# 4_3_MCU_RGB.net
KiCad netlist of a schematic drawn in Altium Designer
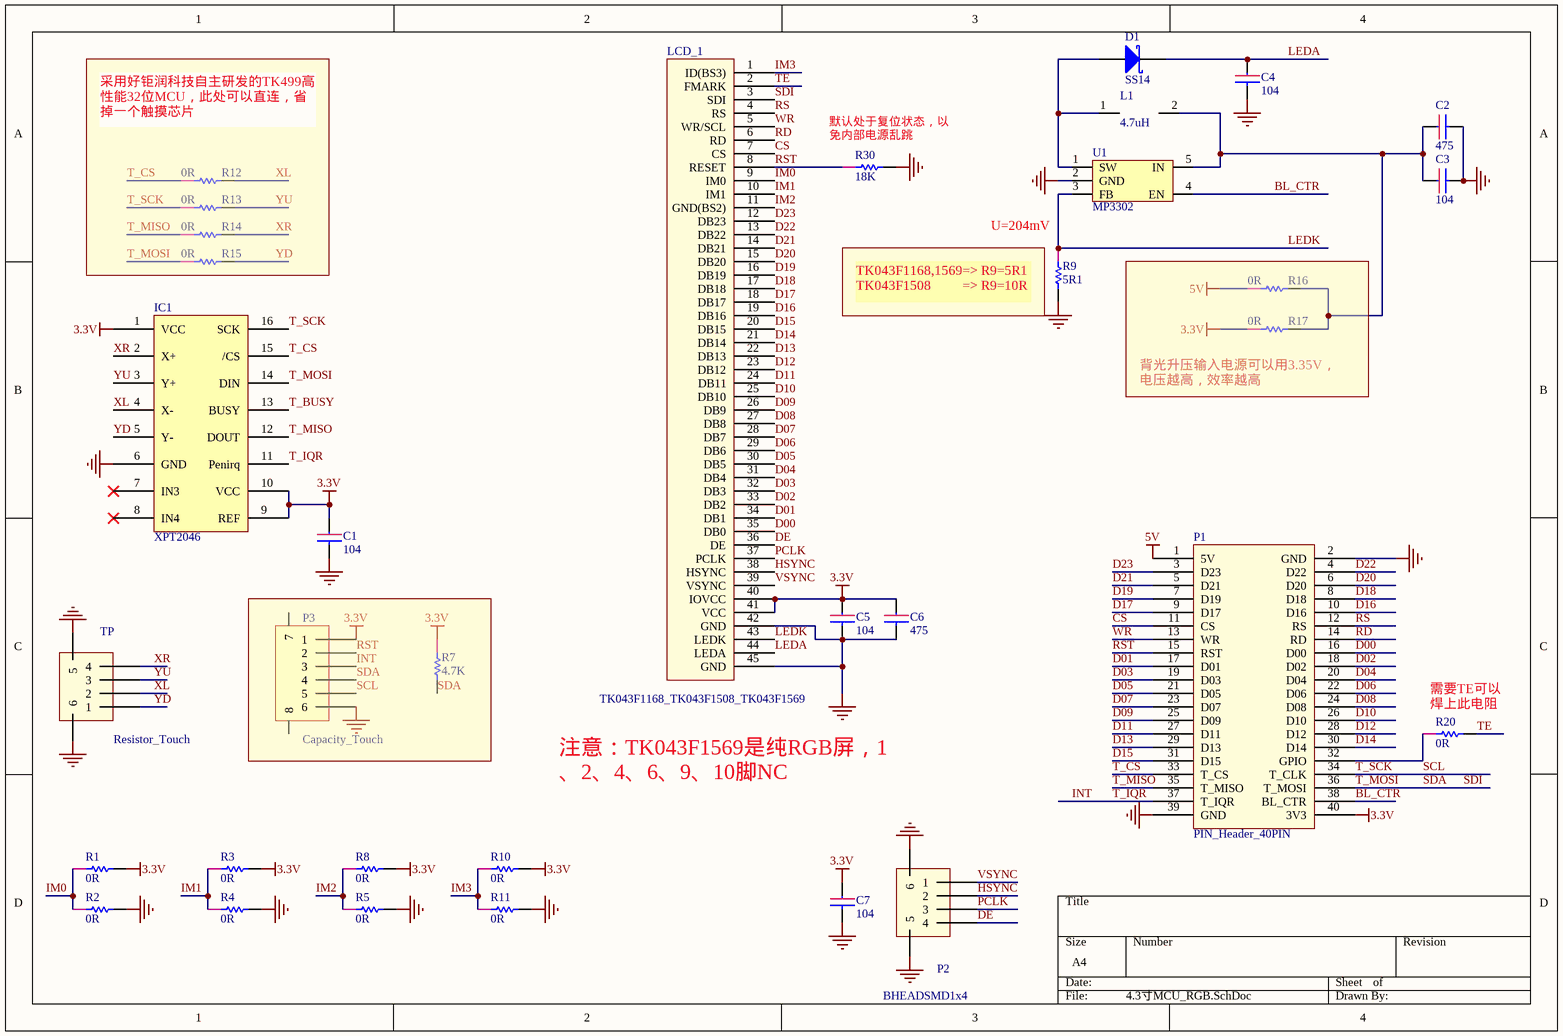
[diagram p0: 4.3寸MCU_RGB.SchDoc]

(export (version "E")
  (design (tool "Eeschema 10.0.6"))
  (components
    (comp (ref "C1") (value "104") (footprint "C0603-1") (libsource (lib "Tiky") (part "cap")))
    (comp (ref "C2") (value "475") (footprint "C0603-2") (libsource (lib "Tiky") (part "cap")))
    (comp (ref "C3") (value "104") (footprint "C0603-1") (libsource (lib "Tiky") (part "cap")))
    (comp (ref "C4") (value "104") (footprint "C0603-2") (libsource (lib "Tiky") (part "cap")))
    (comp (ref "C5") (value "104") (footprint "C0603-1") (libsource (lib "Tiky") (part "cap")))
    (comp (ref "C6") (value "475") (footprint "C0603-2") (libsource (lib "Tiky") (part "cap")))
    (comp (ref "C7") (value "104") (footprint "C0603-1") (libsource (lib "Tiky") (part "cap")))
    (comp (ref "D1")
      (value "SS14")
      (footprint "SOD123")
      (description "Schottky Diode")
      (fields (field (name "PUBLISHER") "Altium Limited"))
      (libsource (lib "Miscellaneous Devices") (part "D Schottky"))
    )
    (comp (ref "IC1") (value "XPT2046") (footprint "SOT403-1") (libsource (lib "Tiky") (part "ADS7843")))
    (comp (ref "L1") (value "4.7uH") (footprint "L1206") (libsource (lib "Tiky") (part "Inductor")))
    (comp (ref "LCD_1")
      (value "TK043F1168_TK043F1508_TK043F1569")
      (footprint "TFT_KGM1066A0")
      (libsource (lib "Tiky") (part "TK043F1168"))
    )
    (comp (ref "P1")
      (value "PIN_Header_40PIN")
      (footprint "P_Head_2x20")
      (libsource (lib "Tiky") (part "PIN_Header_40PIN"))
    )
    (comp (ref "P2")
      (value "BHEADSMD1x4")
      (footprint "BHEADSMD1x4")
      (libsource (lib "") (part "BHEADSMD1x4_1"))
    )
    (comp (ref "P3")
      (value "Capacity_Touch")
      (footprint "TP_Cap_4.3inch")
      (libsource (lib "Tiky") (part "BHEADSMD1x6"))
    )
    (comp (ref "R1") (value "0R") (footprint "R0603") (libsource (lib "Tiky") (part "Resistor")))
    (comp (ref "R2") (value "0R") (footprint "R0603") (libsource (lib "Tiky") (part "Resistor")))
    (comp (ref "R3") (value "0R") (footprint "R0603") (libsource (lib "Tiky") (part "Resistor")))
    (comp (ref "R4") (value "0R") (footprint "R0603") (libsource (lib "Tiky") (part "Resistor")))
    (comp (ref "R5") (value "0R") (footprint "R0603") (libsource (lib "Tiky") (part "Resistor")))
    (comp (ref "R7") (value "4.7K") (footprint "R0603") (libsource (lib "Tiky") (part "Resistor")))
    (comp (ref "R8") (value "0R") (footprint "R0603") (libsource (lib "Tiky") (part "Resistor")))
    (comp (ref "R9") (value "5R1") (footprint "R0603") (libsource (lib "Tiky") (part "Resistor")))
    (comp (ref "R10") (value "0R") (footprint "R0603") (libsource (lib "Tiky") (part "Resistor")))
    (comp (ref "R11") (value "0R") (footprint "R0603") (libsource (lib "Tiky") (part "Resistor")))
    (comp (ref "R12") (value "0R") (footprint "R0402") (libsource (lib "Tiky") (part "Resistor")))
    (comp (ref "R13") (value "0R") (footprint "R0402") (libsource (lib "Tiky") (part "Resistor")))
    (comp (ref "R14") (value "0R") (footprint "R0402") (libsource (lib "Tiky") (part "Resistor")))
    (comp (ref "R15") (value "0R") (footprint "R0402") (libsource (lib "Tiky") (part "Resistor")))
    (comp (ref "R16") (value "0R") (footprint "R0603") (libsource (lib "Tiky") (part "Resistor")))
    (comp (ref "R17") (value "0R") (footprint "R0603") (libsource (lib "Tiky") (part "Resistor")))
    (comp (ref "R20") (value "0R") (footprint "R0603") (libsource (lib "Tiky") (part "Resistor")))
    (comp (ref "R30") (value "18K") (footprint "R0603") (libsource (lib "Tiky") (part "Resistor")))
    (comp (ref "TP")
      (value "Resistor_Touch")
      (footprint "TP_5.0inch")
      (libsource (lib "Tiky") (part "BHEADSMD1x4"))
    )
    (comp (ref "U1") (value "MP3302") (footprint "SOT23-5") (libsource (lib "Tiky") (part "MP3302")))
  )
  (nets
    (net (code "1") (name "/BL_CTR") (class "Default")
      (node (ref "P1") (pin "38") (pinfunction "BL_CTR_38") (pintype "passive"))
      (node (ref "U1") (pin "4") (pinfunction "EN_4") (pintype "passive"))
    )
    (net (code "2") (name "/CS") (class "Default")
      (node (ref "LCD_1") (pin "7") (pinfunction "CS_7") (pintype "passive"))
      (node (ref "P1") (pin "11") (pinfunction "CS_11") (pintype "passive"))
    )
    (net (code "3") (name "/D00") (class "Default")
      (node (ref "LCD_1") (pin "35") (pinfunction "DB0_35") (pintype "passive"))
      (node (ref "P1") (pin "16") (pinfunction "D00_16") (pintype "passive"))
    )
    (net (code "4") (name "/D01") (class "Default")
      (node (ref "LCD_1") (pin "34") (pinfunction "DB1_34") (pintype "passive"))
      (node (ref "P1") (pin "17") (pinfunction "D01_17") (pintype "passive"))
    )
    (net (code "5") (name "/D02") (class "Default")
      (node (ref "LCD_1") (pin "33") (pinfunction "DB2_33") (pintype "passive"))
      (node (ref "P1") (pin "18") (pinfunction "D02_18") (pintype "passive"))
    )
    (net (code "6") (name "/D03") (class "Default")
      (node (ref "LCD_1") (pin "32") (pinfunction "DB3_32") (pintype "passive"))
      (node (ref "P1") (pin "19") (pinfunction "D03_19") (pintype "passive"))
    )
    (net (code "7") (name "/D04") (class "Default")
      (node (ref "LCD_1") (pin "31") (pinfunction "DB4_31") (pintype "passive"))
      (node (ref "P1") (pin "20") (pinfunction "D04_20") (pintype "passive"))
    )
    (net (code "8") (name "/D05") (class "Default")
      (node (ref "LCD_1") (pin "30") (pinfunction "DB5_30") (pintype "passive"))
      (node (ref "P1") (pin "21") (pinfunction "D05_21") (pintype "passive"))
    )
    (net (code "9") (name "/D06") (class "Default")
      (node (ref "LCD_1") (pin "29") (pinfunction "DB6_29") (pintype "passive"))
      (node (ref "P1") (pin "22") (pinfunction "D06_22") (pintype "passive"))
    )
    (net (code "10") (name "/D07") (class "Default")
      (node (ref "LCD_1") (pin "28") (pinfunction "DB7_28") (pintype "passive"))
      (node (ref "P1") (pin "23") (pinfunction "D07_23") (pintype "passive"))
    )
    (net (code "11") (name "/D08") (class "Default")
      (node (ref "LCD_1") (pin "27") (pinfunction "DB8_27") (pintype "passive"))
      (node (ref "P1") (pin "24") (pinfunction "D08_24") (pintype "passive"))
    )
    (net (code "12") (name "/D09") (class "Default")
      (node (ref "LCD_1") (pin "26") (pinfunction "DB9_26") (pintype "passive"))
      (node (ref "P1") (pin "25") (pinfunction "D09_25") (pintype "passive"))
    )
    (net (code "13") (name "/D10") (class "Default")
      (node (ref "LCD_1") (pin "25") (pinfunction "DB10_25") (pintype "passive"))
      (node (ref "P1") (pin "26") (pinfunction "D10_26") (pintype "passive"))
    )
    (net (code "14") (name "/D11") (class "Default")
      (node (ref "LCD_1") (pin "24") (pinfunction "DB11_24") (pintype "passive"))
      (node (ref "P1") (pin "27") (pinfunction "D11_27") (pintype "passive"))
    )
    (net (code "15") (name "/D12") (class "Default")
      (node (ref "LCD_1") (pin "23") (pinfunction "DB12_23") (pintype "passive"))
      (node (ref "P1") (pin "28") (pinfunction "D12_28") (pintype "passive"))
    )
    (net (code "16") (name "/D13") (class "Default")
      (node (ref "LCD_1") (pin "22") (pinfunction "DB13_22") (pintype "passive"))
      (node (ref "P1") (pin "29") (pinfunction "D13_29") (pintype "passive"))
    )
    (net (code "17") (name "/D14") (class "Default")
      (node (ref "LCD_1") (pin "21") (pinfunction "DB14_21") (pintype "passive"))
      (node (ref "P1") (pin "30") (pinfunction "D14_30") (pintype "passive"))
    )
    (net (code "18") (name "/D15") (class "Default")
      (node (ref "LCD_1") (pin "20") (pinfunction "DB15_20") (pintype "passive"))
      (node (ref "P1") (pin "31") (pinfunction "D15_31") (pintype "passive"))
    )
    (net (code "19") (name "/D16") (class "Default")
      (node (ref "LCD_1") (pin "19") (pinfunction "DB16_19") (pintype "passive"))
      (node (ref "P1") (pin "10") (pinfunction "D16_10") (pintype "passive"))
    )
    (net (code "20") (name "/D17") (class "Default")
      (node (ref "LCD_1") (pin "18") (pinfunction "DB17_18") (pintype "passive"))
      (node (ref "P1") (pin "9") (pinfunction "D17_9") (pintype "passive"))
    )
    (net (code "21") (name "/D18") (class "Default")
      (node (ref "LCD_1") (pin "17") (pinfunction "DB18_17") (pintype "passive"))
      (node (ref "P1") (pin "8") (pinfunction "D18_8") (pintype "passive"))
    )
    (net (code "22") (name "/D19") (class "Default")
      (node (ref "LCD_1") (pin "16") (pinfunction "DB19_16") (pintype "passive"))
      (node (ref "P1") (pin "7") (pinfunction "D19_7") (pintype "passive"))
    )
    (net (code "23") (name "/D20") (class "Default")
      (node (ref "LCD_1") (pin "15") (pinfunction "DB20_15") (pintype "passive"))
      (node (ref "P1") (pin "6") (pinfunction "D20_6") (pintype "passive"))
    )
    (net (code "24") (name "/D21") (class "Default")
      (node (ref "LCD_1") (pin "14") (pinfunction "DB21_14") (pintype "passive"))
      (node (ref "P1") (pin "5") (pinfunction "D21_5") (pintype "passive"))
    )
    (net (code "25") (name "/D22") (class "Default")
      (node (ref "LCD_1") (pin "13") (pinfunction "DB22_13") (pintype "passive"))
      (node (ref "P1") (pin "4") (pinfunction "D22_4") (pintype "passive"))
    )
    (net (code "26") (name "/D23") (class "Default")
      (node (ref "LCD_1") (pin "12") (pinfunction "DB23_12") (pintype "passive"))
      (node (ref "P1") (pin "3") (pinfunction "D23_3") (pintype "passive"))
    )
    (net (code "27") (name "/DE") (class "Default")
      (node (ref "LCD_1") (pin "36") (pinfunction "DE_36") (pintype "passive"))
      (node (ref "P2") (pin "4") (pinfunction "4_4") (pintype "passive"))
    )
    (net (code "28") (name "/HSYNC") (class "Default")
      (node (ref "LCD_1") (pin "38") (pinfunction "HSYNC_38") (pintype "passive"))
      (node (ref "P2") (pin "2") (pinfunction "2_2") (pintype "passive"))
    )
    (net (code "29") (name "/IM0") (class "Default")
      (node (ref "LCD_1") (pin "9") (pinfunction "IM0_9") (pintype "passive"))
      (node (ref "R1") (pin "1") (pinfunction "1_1") (pintype "passive"))
      (node (ref "R2") (pin "1") (pinfunction "1_1") (pintype "passive"))
    )
    (net (code "30") (name "/IM1") (class "Default")
      (node (ref "LCD_1") (pin "10") (pinfunction "IM1_10") (pintype "passive"))
      (node (ref "R3") (pin "1") (pinfunction "1_1") (pintype "passive"))
      (node (ref "R4") (pin "1") (pinfunction "1_1") (pintype "passive"))
    )
    (net (code "31") (name "/IM2") (class "Default")
      (node (ref "LCD_1") (pin "11") (pinfunction "GND(BS2)_11") (pintype "passive"))
      (node (ref "R5") (pin "1") (pinfunction "1_1") (pintype "passive"))
      (node (ref "R8") (pin "1") (pinfunction "1_1") (pintype "passive"))
    )
    (net (code "32") (name "/IM3") (class "Default")
      (node (ref "LCD_1") (pin "1") (pinfunction "ID(BS3)_1") (pintype "passive"))
      (node (ref "R10") (pin "1") (pinfunction "1_1") (pintype "passive"))
      (node (ref "R11") (pin "1") (pinfunction "1_1") (pintype "passive"))
    )
    (net (code "33") (name "/INT") (class "Default")
      (node (ref "IC1") (pin "11") (pinfunction "Penirq_11") (pintype "passive"))
      (node (ref "P1") (pin "37") (pinfunction "T_IQR_37") (pintype "passive"))
      (node (ref "P3") (pin "3") (pinfunction "3_3") (pintype "passive"))
    )
    (net (code "34") (name "/LEDA") (class "Default")
      (node (ref "C4") (pin "1") (pinfunction "1_1") (pintype "passive"))
      (node (ref "D1") (pin "2") (pinfunction "K_2") (pintype "passive"))
      (node (ref "LCD_1") (pin "44") (pinfunction "LEDA_44") (pintype "passive"))
    )
    (net (code "35") (name "/LEDK") (class "Default")
      (node (ref "LCD_1") (pin "43") (pinfunction "LEDK_43") (pintype "passive"))
      (node (ref "R9") (pin "1") (pinfunction "1_1") (pintype "passive"))
      (node (ref "U1") (pin "3") (pinfunction "FB_3") (pintype "passive"))
    )
    (net (code "36") (name "/PCLK") (class "Default")
      (node (ref "LCD_1") (pin "37") (pinfunction "PCLK_37") (pintype "passive"))
      (node (ref "P2") (pin "3") (pinfunction "3_3") (pintype "passive"))
    )
    (net (code "37") (name "/RD") (class "Default")
      (node (ref "LCD_1") (pin "6") (pinfunction "RD_6") (pintype "passive"))
      (node (ref "P1") (pin "14") (pinfunction "RD_14") (pintype "passive"))
    )
    (net (code "38") (name "/RS") (class "Default")
      (node (ref "LCD_1") (pin "4") (pinfunction "RS_4") (pintype "passive"))
      (node (ref "P1") (pin "12") (pinfunction "RS_12") (pintype "passive"))
    )
    (net (code "39") (name "/RST") (class "Default")
      (node (ref "LCD_1") (pin "8") (pinfunction "RESET_8") (pintype "passive"))
      (node (ref "P1") (pin "15") (pinfunction "RST_15") (pintype "passive"))
      (node (ref "P3") (pin "2") (pinfunction "2_2") (pintype "passive"))
      (node (ref "R30") (pin "1") (pinfunction "1_1") (pintype "passive"))
    )
    (net (code "40") (name "/SCL") (class "Default")
      (node (ref "IC1") (pin "16") (pinfunction "SCK_16") (pintype "passive"))
      (node (ref "P1") (pin "34") (pinfunction "T_CLK_34") (pintype "passive"))
      (node (ref "P3") (pin "5") (pinfunction "5_5") (pintype "passive"))
      (node (ref "R13") (pin "1") (pinfunction "1_1") (pintype "passive"))
    )
    (net (code "41") (name "/SDA") (class "Default")
      (node (ref "IC1") (pin "14") (pinfunction "DIN_14") (pintype "passive"))
      (node (ref "LCD_1") (pin "3") (pinfunction "SDI_3") (pintype "passive"))
      (node (ref "P1") (pin "36") (pinfunction "T_MOSI_36") (pintype "passive"))
      (node (ref "P3") (pin "4") (pinfunction "4_4") (pintype "passive"))
      (node (ref "R15") (pin "1") (pinfunction "1_1") (pintype "passive"))
      (node (ref "R7") (pin "2") (pinfunction "2_2") (pintype "passive"))
    )
    (net (code "42") (name "/TE") (class "Default")
      (node (ref "LCD_1") (pin "2") (pinfunction "FMARK_2") (pintype "passive"))
      (node (ref "R20") (pin "2") (pinfunction "2_2") (pintype "passive"))
    )
    (net (code "43") (name "/T_BUSY") (class "Default")
      (node (ref "IC1") (pin "13") (pinfunction "BUSY_13") (pintype "passive"))
    )
    (net (code "44") (name "/T_CS") (class "Default")
      (node (ref "IC1") (pin "15") (pinfunction "/CS_15") (pintype "passive"))
      (node (ref "P1") (pin "33") (pinfunction "T_CS_33") (pintype "passive"))
      (node (ref "R12") (pin "1") (pinfunction "1_1") (pintype "passive"))
    )
    (net (code "45") (name "/T_MISO") (class "Default")
      (node (ref "IC1") (pin "12") (pinfunction "DOUT_12") (pintype "passive"))
      (node (ref "P1") (pin "35") (pinfunction "T_MISO_35") (pintype "passive"))
      (node (ref "R14") (pin "1") (pinfunction "1_1") (pintype "passive"))
    )
    (net (code "46") (name "/VSYNC") (class "Default")
      (node (ref "LCD_1") (pin "39") (pinfunction "VSYNC_39") (pintype "passive"))
      (node (ref "P2") (pin "1") (pinfunction "1_1") (pintype "passive"))
    )
    (net (code "47") (name "/WR") (class "Default")
      (node (ref "LCD_1") (pin "5") (pinfunction "WR/SCL_5") (pintype "passive"))
      (node (ref "P1") (pin "13") (pinfunction "WR_13") (pintype "passive"))
    )
    (net (code "48") (name "/XL") (class "Default")
      (node (ref "IC1") (pin "4") (pinfunction "X-_4") (pintype "passive"))
      (node (ref "R12") (pin "2") (pinfunction "2_2") (pintype "passive"))
      (node (ref "TP") (pin "2") (pinfunction "2_2") (pintype "passive"))
    )
    (net (code "49") (name "/XR") (class "Default")
      (node (ref "IC1") (pin "2") (pinfunction "X+_2") (pintype "passive"))
      (node (ref "R14") (pin "2") (pinfunction "2_2") (pintype "passive"))
      (node (ref "TP") (pin "4") (pinfunction "4_4") (pintype "passive"))
    )
    (net (code "50") (name "/YD") (class "Default")
      (node (ref "IC1") (pin "5") (pinfunction "Y-_5") (pintype "passive"))
      (node (ref "R15") (pin "2") (pinfunction "2_2") (pintype "passive"))
      (node (ref "TP") (pin "1") (pinfunction "1_1") (pintype "passive"))
    )
    (net (code "51") (name "/YU") (class "Default")
      (node (ref "IC1") (pin "3") (pinfunction "Y+_3") (pintype "passive"))
      (node (ref "R13") (pin "2") (pinfunction "2_2") (pintype "passive"))
      (node (ref "TP") (pin "3") (pinfunction "3_3") (pintype "passive"))
    )
    (net (code "52") (name "3.3V") (class "Default")
      (node (ref "C1") (pin "1") (pinfunction "1_1") (pintype "passive"))
      (node (ref "C5") (pin "1") (pinfunction "1_1") (pintype "passive"))
      (node (ref "C6") (pin "1") (pinfunction "1_1") (pintype "passive"))
      (node (ref "C7") (pin "1") (pinfunction "1_1") (pintype "passive"))
      (node (ref "IC1") (pin "1") (pinfunction "VCC_1") (pintype "passive"))
      (node (ref "IC1") (pin "10") (pinfunction "VCC_10") (pintype "passive"))
      (node (ref "IC1") (pin "9") (pinfunction "REF_9") (pintype "passive"))
      (node (ref "LCD_1") (pin "40") (pinfunction "IOVCC_40") (pintype "passive"))
      (node (ref "LCD_1") (pin "41") (pinfunction "VCC_41") (pintype "passive"))
      (node (ref "P1") (pin "40") (pinfunction "3V3_40") (pintype "passive"))
      (node (ref "P3") (pin "1") (pinfunction "1_1") (pintype "passive"))
      (node (ref "R1") (pin "2") (pinfunction "2_2") (pintype "passive"))
      (node (ref "R10") (pin "2") (pinfunction "2_2") (pintype "passive"))
      (node (ref "R17") (pin "1") (pinfunction "1_1") (pintype "passive"))
      (node (ref "R3") (pin "2") (pinfunction "2_2") (pintype "passive"))
      (node (ref "R7") (pin "1") (pinfunction "1_1") (pintype "passive"))
      (node (ref "R8") (pin "2") (pinfunction "2_2") (pintype "passive"))
    )
    (net (code "53") (name "5V") (class "Default")
      (node (ref "P1") (pin "1") (pinfunction "5V_1") (pintype "passive"))
      (node (ref "R16") (pin "1") (pinfunction "1_1") (pintype "passive"))
    )
    (net (code "54") (name "GND") (class "Default")
      (node (ref "C1") (pin "2") (pinfunction "2_2") (pintype "passive"))
      (node (ref "C2") (pin "2") (pinfunction "2_2") (pintype "passive"))
      (node (ref "C3") (pin "2") (pinfunction "2_2") (pintype "passive"))
      (node (ref "C4") (pin "2") (pinfunction "2_2") (pintype "passive"))
      (node (ref "C5") (pin "2") (pinfunction "2_2") (pintype "passive"))
      (node (ref "C6") (pin "2") (pinfunction "2_2") (pintype "passive"))
      (node (ref "C7") (pin "2") (pinfunction "2_2") (pintype "passive"))
      (node (ref "IC1") (pin "6") (pinfunction "GND_6") (pintype "passive"))
      (node (ref "LCD_1") (pin "42") (pinfunction "GND_42") (pintype "passive"))
      (node (ref "LCD_1") (pin "45") (pinfunction "GND_45") (pintype "passive"))
      (node (ref "P1") (pin "2") (pinfunction "GND_2") (pintype "passive"))
      (node (ref "P1") (pin "39") (pinfunction "GND_39") (pintype "passive"))
      (node (ref "P2") (pin "5") (pinfunction "5_5") (pintype "passive"))
      (node (ref "P2") (pin "6") (pinfunction "6_6") (pintype "passive"))
      (node (ref "P3") (pin "6") (pinfunction "6_6") (pintype "passive"))
      (node (ref "R11") (pin "2") (pinfunction "2_2") (pintype "passive"))
      (node (ref "R2") (pin "2") (pinfunction "2_2") (pintype "passive"))
      (node (ref "R30") (pin "2") (pinfunction "2_2") (pintype "passive"))
      (node (ref "R4") (pin "2") (pinfunction "2_2") (pintype "passive"))
      (node (ref "R5") (pin "2") (pinfunction "2_2") (pintype "passive"))
      (node (ref "R9") (pin "2") (pinfunction "2_2") (pintype "passive"))
      (node (ref "TP") (pin "5") (pinfunction "5_5") (pintype "passive"))
      (node (ref "TP") (pin "6") (pinfunction "6_6") (pintype "passive"))
      (node (ref "U1") (pin "2") (pinfunction "GND_2") (pintype "passive"))
    )
    (net (code "55") (name "Net-(D1-A)") (class "Default")
      (node (ref "D1") (pin "1") (pinfunction "A_1") (pintype "passive"))
      (node (ref "L1") (pin "1") (pinfunction "1_1") (pintype "passive"))
      (node (ref "U1") (pin "1") (pinfunction "SW_1") (pintype "passive"))
    )
    (net (code "56") (name "Net-(P1-GPIO)") (class "Default")
      (node (ref "P1") (pin "32") (pinfunction "GPIO_32") (pintype "passive"))
      (node (ref "R20") (pin "1") (pinfunction "1_1") (pintype "passive"))
    )
    (net (code "57") (name "Net-(U1-IN)") (class "Default")
      (node (ref "C2") (pin "1") (pinfunction "1_1") (pintype "passive"))
      (node (ref "C3") (pin "1") (pinfunction "1_1") (pintype "passive"))
      (node (ref "L1") (pin "2") (pinfunction "2_2") (pintype "passive"))
      (node (ref "R16") (pin "2") (pinfunction "2_2") (pintype "passive"))
      (node (ref "R17") (pin "2") (pinfunction "2_2") (pintype "passive"))
      (node (ref "U1") (pin "5") (pinfunction "IN_5") (pintype "passive"))
    )
    (net (code "58") (name "unconnected-(IC1-IN3-Pad7)") (class "Default")
      (node (ref "IC1") (pin "7") (pinfunction "IN3_7") (pintype "passive+no_connect"))
    )
    (net (code "59") (name "unconnected-(IC1-IN4-Pad8)") (class "Default")
      (node (ref "IC1") (pin "8") (pinfunction "IN4_8") (pintype "passive+no_connect"))
    )
    (net (code "60") (name "unconnected-(P3-Pad7)") (class "Default")
      (node (ref "P3") (pin "7") (pinfunction "7_7") (pintype "passive"))
    )
    (net (code "61") (name "unconnected-(P3-Pad8)") (class "Default")
      (node (ref "P3") (pin "8") (pinfunction "8_8") (pintype "passive"))
    )
  )
)
